# Weihnachtsstern.net
KiCad netlist of a schematic drawn in EAGLE
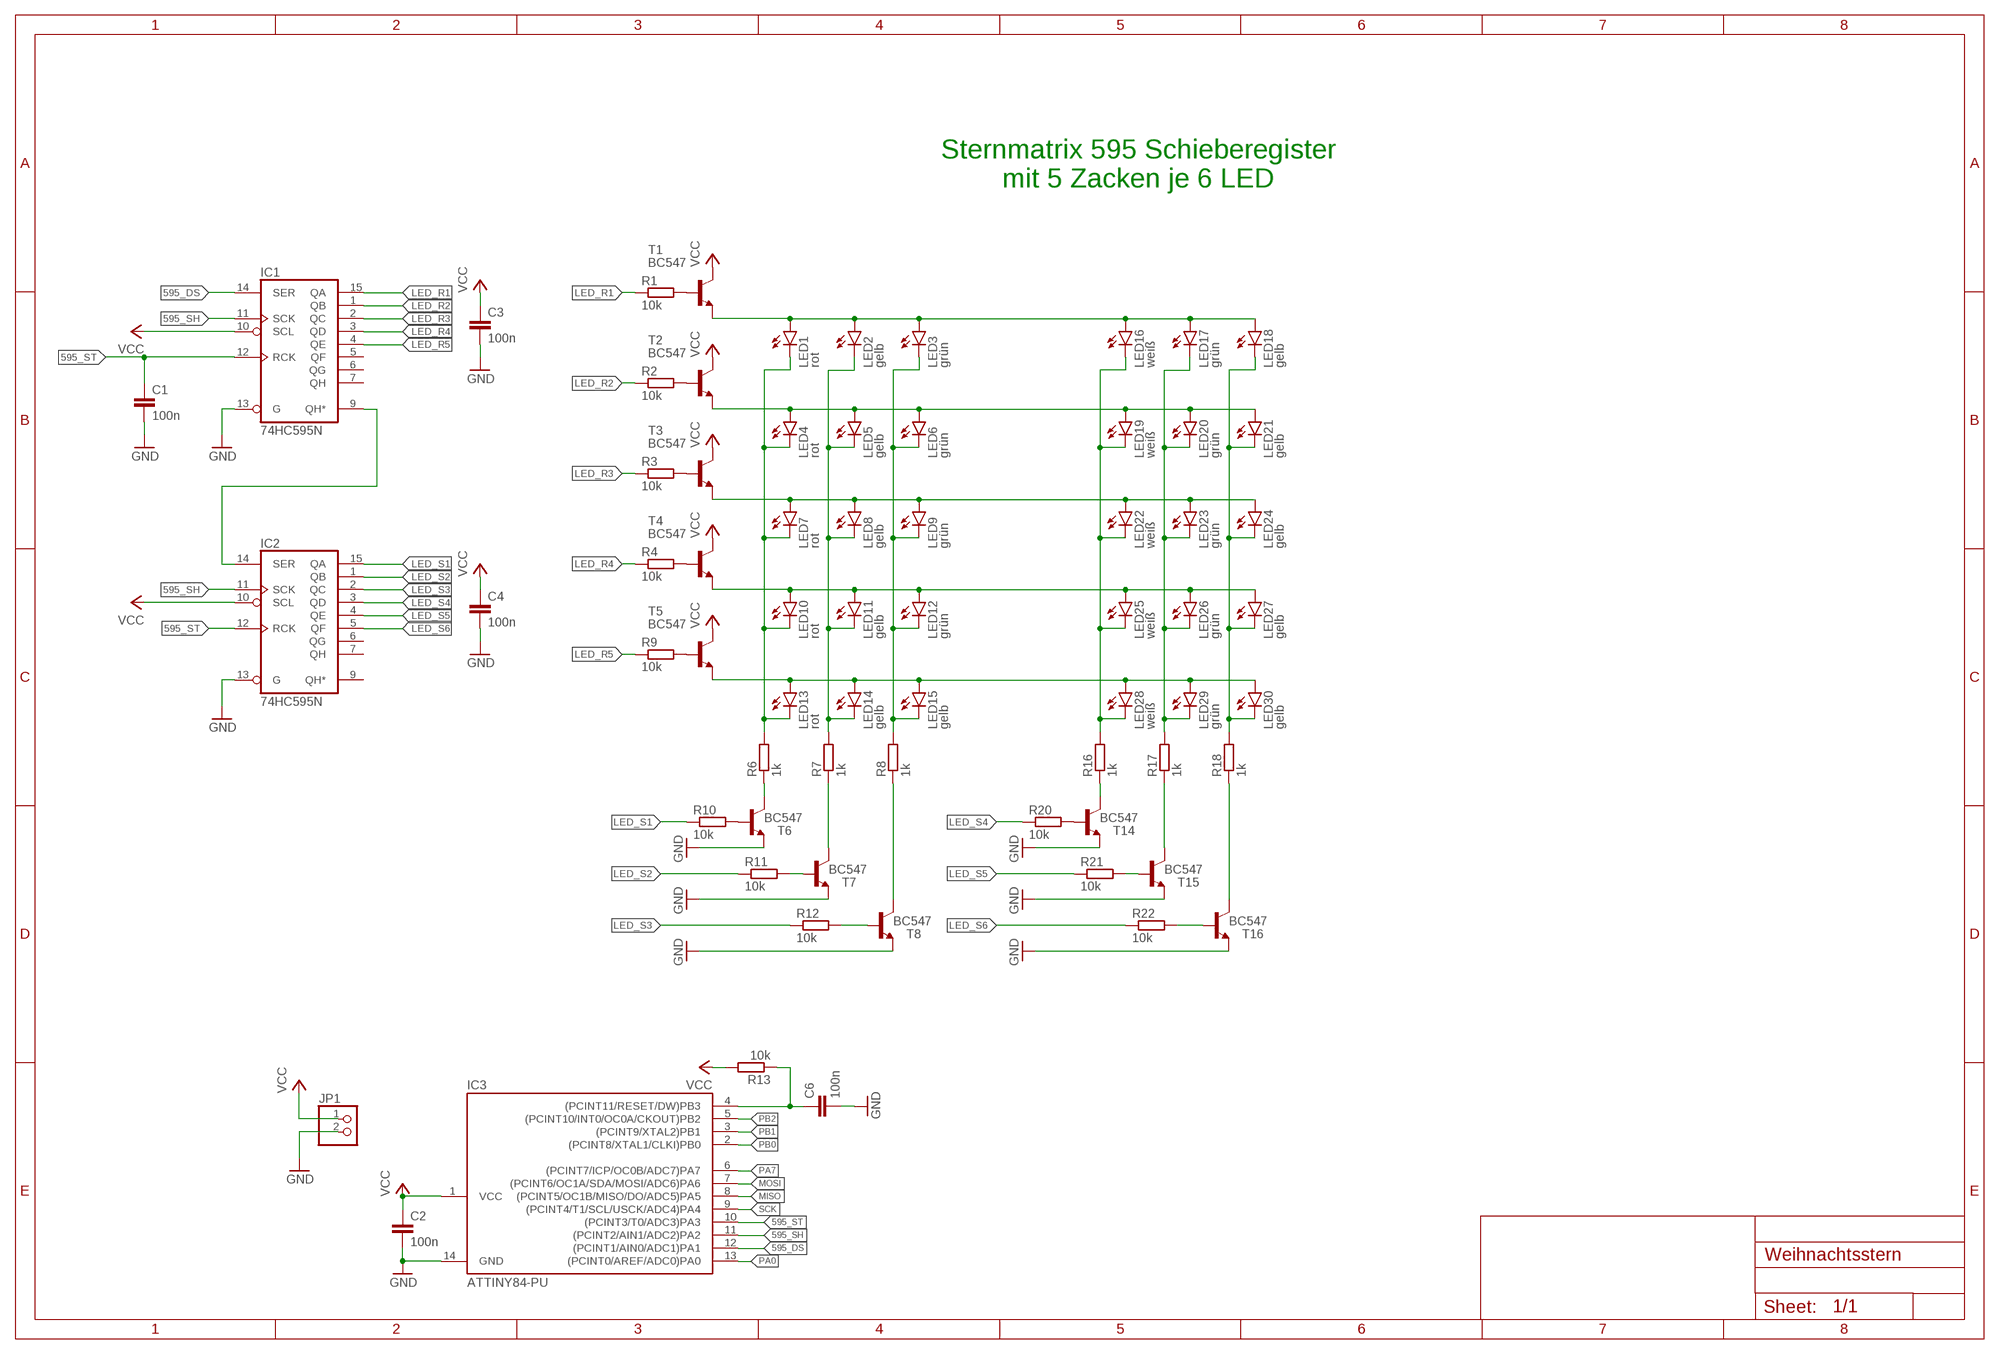
[diagram p0: schematic, sheet 1]

(export (version "E")
  (design (tool "Eeschema 10.0.6"))
  (components
    (comp (ref "C1")
      (value "100n")
      (footprint "eagle-import:C025-024X044")
      (libsource (lib "eagle-import") (part "C-EU025-024X044"))
    )
    (comp (ref "C2")
      (value "100n")
      (footprint "eagle-import:C025-024X044")
      (libsource (lib "eagle-import") (part "C-EU025-024X044"))
    )
    (comp (ref "C3")
      (value "100n")
      (footprint "eagle-import:C025-024X044")
      (libsource (lib "eagle-import") (part "C-EU025-024X044"))
    )
    (comp (ref "C4")
      (value "100n")
      (footprint "eagle-import:C025-024X044")
      (libsource (lib "eagle-import") (part "C-EU025-024X044"))
    )
    (comp (ref "C6")
      (value "100n")
      (footprint "eagle-import:C025-024X044")
      (libsource (lib "eagle-import") (part "C-EU025-024X044"))
    )
    (comp (ref "IC1")
      (value "74HC595N")
      (footprint "eagle-import:DIL16")
      (libsource (lib "eagle-import") (part "74595NHC"))
    )
    (comp (ref "IC2")
      (value "74HC595N")
      (footprint "eagle-import:DIL16")
      (libsource (lib "eagle-import") (part "74595NHC"))
    )
    (comp (ref "IC3")
      (value "ATTINY84-PU")
      (footprint "eagle-import:DIL14")
      (libsource (lib "eagle-import") (part "ATTINY24/44/84-PU"))
    )
    (comp (ref "JP1")
      (value "PINHD-1X2")
      (footprint "eagle-import:1X02")
      (libsource (lib "eagle-import") (part "PINHD-1X2"))
    )
    (comp (ref "LED1")
      (value "rot")
      (footprint "eagle-import:LED3MM")
      (libsource (lib "eagle-import") (part "LED3MM"))
    )
    (comp (ref "LED2")
      (value "gelb")
      (footprint "eagle-import:LED3MM")
      (libsource (lib "eagle-import") (part "LED3MM"))
    )
    (comp (ref "LED3")
      (value "grün")
      (footprint "eagle-import:LED3MM")
      (libsource (lib "eagle-import") (part "LED3MM"))
    )
    (comp (ref "LED4")
      (value "rot")
      (footprint "eagle-import:LED3MM")
      (libsource (lib "eagle-import") (part "LED3MM"))
    )
    (comp (ref "LED5")
      (value "gelb")
      (footprint "eagle-import:LED3MM")
      (libsource (lib "eagle-import") (part "LED3MM"))
    )
    (comp (ref "LED6")
      (value "grün")
      (footprint "eagle-import:LED3MM")
      (libsource (lib "eagle-import") (part "LED3MM"))
    )
    (comp (ref "LED7")
      (value "rot")
      (footprint "eagle-import:LED3MM")
      (libsource (lib "eagle-import") (part "LED3MM"))
    )
    (comp (ref "LED8")
      (value "gelb")
      (footprint "eagle-import:LED3MM")
      (libsource (lib "eagle-import") (part "LED3MM"))
    )
    (comp (ref "LED9")
      (value "grün")
      (footprint "eagle-import:LED3MM")
      (libsource (lib "eagle-import") (part "LED3MM"))
    )
    (comp (ref "LED10")
      (value "rot")
      (footprint "eagle-import:LED3MM")
      (libsource (lib "eagle-import") (part "LED3MM"))
    )
    (comp (ref "LED11")
      (value "gelb")
      (footprint "eagle-import:LED3MM")
      (libsource (lib "eagle-import") (part "LED3MM"))
    )
    (comp (ref "LED12")
      (value "grün")
      (footprint "eagle-import:LED3MM")
      (libsource (lib "eagle-import") (part "LED3MM"))
    )
    (comp (ref "LED13")
      (value "rot")
      (footprint "eagle-import:LED3MM")
      (libsource (lib "eagle-import") (part "LED3MM"))
    )
    (comp (ref "LED14")
      (value "gelb")
      (footprint "eagle-import:LED3MM")
      (libsource (lib "eagle-import") (part "LED3MM"))
    )
    (comp (ref "LED15")
      (value "gelb")
      (footprint "eagle-import:LED3MM")
      (libsource (lib "eagle-import") (part "LED3MM"))
    )
    (comp (ref "LED16")
      (value "weiß")
      (footprint "eagle-import:LED3MM")
      (libsource (lib "eagle-import") (part "LED3MM"))
    )
    (comp (ref "LED17")
      (value "grün")
      (footprint "eagle-import:LED3MM")
      (libsource (lib "eagle-import") (part "LED3MM"))
    )
    (comp (ref "LED18")
      (value "gelb")
      (footprint "eagle-import:LED3MM")
      (libsource (lib "eagle-import") (part "LED3MM"))
    )
    (comp (ref "LED19")
      (value "weiß")
      (footprint "eagle-import:LED3MM")
      (libsource (lib "eagle-import") (part "LED3MM"))
    )
    (comp (ref "LED20")
      (value "grün")
      (footprint "eagle-import:LED3MM")
      (libsource (lib "eagle-import") (part "LED3MM"))
    )
    (comp (ref "LED21")
      (value "gelb")
      (footprint "eagle-import:LED3MM")
      (libsource (lib "eagle-import") (part "LED3MM"))
    )
    (comp (ref "LED22")
      (value "weiß")
      (footprint "eagle-import:LED3MM")
      (libsource (lib "eagle-import") (part "LED3MM"))
    )
    (comp (ref "LED23")
      (value "grün")
      (footprint "eagle-import:LED3MM")
      (libsource (lib "eagle-import") (part "LED3MM"))
    )
    (comp (ref "LED24")
      (value "gelb")
      (footprint "eagle-import:LED3MM")
      (libsource (lib "eagle-import") (part "LED3MM"))
    )
    (comp (ref "LED25")
      (value "weiß")
      (footprint "eagle-import:LED3MM")
      (libsource (lib "eagle-import") (part "LED3MM"))
    )
    (comp (ref "LED26")
      (value "grün")
      (footprint "eagle-import:LED3MM")
      (libsource (lib "eagle-import") (part "LED3MM"))
    )
    (comp (ref "LED27")
      (value "gelb")
      (footprint "eagle-import:LED3MM")
      (libsource (lib "eagle-import") (part "LED3MM"))
    )
    (comp (ref "LED28")
      (value "weiß")
      (footprint "eagle-import:LED3MM")
      (libsource (lib "eagle-import") (part "LED3MM"))
    )
    (comp (ref "LED29")
      (value "grün")
      (footprint "eagle-import:LED3MM")
      (libsource (lib "eagle-import") (part "LED3MM"))
    )
    (comp (ref "LED30")
      (value "gelb")
      (footprint "eagle-import:LED3MM")
      (libsource (lib "eagle-import") (part "LED3MM"))
    )
    (comp (ref "R1")
      (value "10k")
      (footprint "eagle-import:0204_5")
      (libsource (lib "eagle-import") (part "R-EU_0204/5"))
    )
    (comp (ref "R2")
      (value "10k")
      (footprint "eagle-import:0204_5")
      (libsource (lib "eagle-import") (part "R-EU_0204/5"))
    )
    (comp (ref "R3")
      (value "10k")
      (footprint "eagle-import:0204_5")
      (libsource (lib "eagle-import") (part "R-EU_0204/5"))
    )
    (comp (ref "R4")
      (value "10k")
      (footprint "eagle-import:0204_5")
      (libsource (lib "eagle-import") (part "R-EU_0204/5"))
    )
    (comp (ref "R6")
      (value "1k")
      (footprint "eagle-import:0204_5")
      (libsource (lib "eagle-import") (part "R-EU_0204/5"))
    )
    (comp (ref "R7")
      (value "1k")
      (footprint "eagle-import:0204_5")
      (libsource (lib "eagle-import") (part "R-EU_0204/5"))
    )
    (comp (ref "R8")
      (value "1k")
      (footprint "eagle-import:0204_5")
      (libsource (lib "eagle-import") (part "R-EU_0204/5"))
    )
    (comp (ref "R9")
      (value "10k")
      (footprint "eagle-import:0204_5")
      (libsource (lib "eagle-import") (part "R-EU_0204/5"))
    )
    (comp (ref "R10")
      (value "10k")
      (footprint "eagle-import:0204_5")
      (libsource (lib "eagle-import") (part "R-EU_0204/5"))
    )
    (comp (ref "R11")
      (value "10k")
      (footprint "eagle-import:0204_5")
      (libsource (lib "eagle-import") (part "R-EU_0204/5"))
    )
    (comp (ref "R12")
      (value "10k")
      (footprint "eagle-import:0204_5")
      (libsource (lib "eagle-import") (part "R-EU_0204/5"))
    )
    (comp (ref "R13")
      (value "10k")
      (footprint "eagle-import:0204_5")
      (libsource (lib "eagle-import") (part "R-EU_0204/5"))
    )
    (comp (ref "R16")
      (value "1k")
      (footprint "eagle-import:0204_5")
      (libsource (lib "eagle-import") (part "R-EU_0204/5"))
    )
    (comp (ref "R17")
      (value "1k")
      (footprint "eagle-import:0204_5")
      (libsource (lib "eagle-import") (part "R-EU_0204/5"))
    )
    (comp (ref "R18")
      (value "1k")
      (footprint "eagle-import:0204_5")
      (libsource (lib "eagle-import") (part "R-EU_0204/5"))
    )
    (comp (ref "R20")
      (value "10k")
      (footprint "eagle-import:0204_5")
      (libsource (lib "eagle-import") (part "R-EU_0204/5"))
    )
    (comp (ref "R21")
      (value "10k")
      (footprint "eagle-import:0204_5")
      (libsource (lib "eagle-import") (part "R-EU_0204/5"))
    )
    (comp (ref "R22")
      (value "10k")
      (footprint "eagle-import:0204_5")
      (libsource (lib "eagle-import") (part "R-EU_0204/5"))
    )
    (comp (ref "T1")
      (value "BC547")
      (footprint "eagle-import:TO92")
      (libsource (lib "eagle-import") (part "BC547"))
    )
    (comp (ref "T2")
      (value "BC547")
      (footprint "eagle-import:TO92")
      (libsource (lib "eagle-import") (part "BC547"))
    )
    (comp (ref "T3")
      (value "BC547")
      (footprint "eagle-import:TO92")
      (libsource (lib "eagle-import") (part "BC547"))
    )
    (comp (ref "T4")
      (value "BC547")
      (footprint "eagle-import:TO92")
      (libsource (lib "eagle-import") (part "BC547"))
    )
    (comp (ref "T5")
      (value "BC547")
      (footprint "eagle-import:TO92")
      (libsource (lib "eagle-import") (part "-NPN-TO92"))
    )
    (comp (ref "T6")
      (value "BC547")
      (footprint "eagle-import:TO92")
      (libsource (lib "eagle-import") (part "BC547"))
    )
    (comp (ref "T7")
      (value "BC547")
      (footprint "eagle-import:TO92")
      (libsource (lib "eagle-import") (part "BC547"))
    )
    (comp (ref "T8")
      (value "BC547")
      (footprint "eagle-import:TO92")
      (libsource (lib "eagle-import") (part "BC547"))
    )
    (comp (ref "T14")
      (value "BC547")
      (footprint "eagle-import:TO92")
      (libsource (lib "eagle-import") (part "BC547"))
    )
    (comp (ref "T15")
      (value "BC547")
      (footprint "eagle-import:TO92")
      (libsource (lib "eagle-import") (part "BC547"))
    )
    (comp (ref "T16")
      (value "BC547")
      (footprint "eagle-import:TO92")
      (libsource (lib "eagle-import") (part "BC547"))
    )
  )
  (nets
    (net (code "1") (name "595_DS") (class "Default")
      (node (ref "IC1") (pin "14") (pinfunction "SER_14") (pintype "input"))
      (node (ref "IC3") (pin "12") (pinfunction "(PCINT1/AIN0/ADC1)PA1_12") (pintype "bidirectional"))
    )
    (net (code "2") (name "595_SH") (class "Default")
      (node (ref "IC1") (pin "11") (pinfunction "SCK_11") (pintype "input"))
      (node (ref "IC2") (pin "11") (pinfunction "SCK_11") (pintype "input"))
      (node (ref "IC3") (pin "11") (pinfunction "(PCINT2/AIN1/ADC2)PA2_11") (pintype "bidirectional"))
    )
    (net (code "3") (name "595_ST") (class "Default")
      (node (ref "C1") (pin "1") (pinfunction "1_1") (pintype "passive"))
      (node (ref "IC1") (pin "12") (pinfunction "RCK_12") (pintype "input"))
      (node (ref "IC2") (pin "12") (pinfunction "RCK_12") (pintype "input"))
      (node (ref "IC3") (pin "10") (pinfunction "(PCINT3/T0/ADC3)PA3_10") (pintype "bidirectional"))
    )
    (net (code "4") (name "GND") (class "Default")
      (node (ref "C1") (pin "2") (pinfunction "2_2") (pintype "passive"))
      (node (ref "C2") (pin "2") (pinfunction "2_2") (pintype "passive"))
      (node (ref "C3") (pin "2") (pinfunction "2_2") (pintype "passive"))
      (node (ref "C4") (pin "2") (pinfunction "2_2") (pintype "passive"))
      (node (ref "C6") (pin "2") (pinfunction "2_2") (pintype "passive"))
      (node (ref "IC1") (pin "13") (pinfunction "G_13") (pintype "input"))
      (node (ref "IC2") (pin "13") (pinfunction "G_13") (pintype "input"))
      (node (ref "IC3") (pin "14") (pinfunction "GND_14") (pintype "power_in"))
      (node (ref "JP1") (pin "2") (pinfunction "2_2") (pintype "passive"))
      (node (ref "T14") (pin "1") (pinfunction "E_1") (pintype "passive"))
      (node (ref "T15") (pin "1") (pinfunction "E_1") (pintype "passive"))
      (node (ref "T16") (pin "1") (pinfunction "E_1") (pintype "passive"))
      (node (ref "T6") (pin "1") (pinfunction "E_1") (pintype "passive"))
      (node (ref "T7") (pin "1") (pinfunction "E_1") (pintype "passive"))
      (node (ref "T8") (pin "1") (pinfunction "E_1") (pintype "passive"))
    )
    (net (code "5") (name "LED_R1") (class "Default")
      (node (ref "IC1") (pin "15") (pinfunction "QA_15") (pintype "tri_state"))
      (node (ref "R1") (pin "1") (pinfunction "1_1") (pintype "passive"))
    )
    (net (code "6") (name "LED_R2") (class "Default")
      (node (ref "IC1") (pin "1") (pinfunction "QB_1") (pintype "tri_state"))
      (node (ref "R2") (pin "1") (pinfunction "1_1") (pintype "passive"))
    )
    (net (code "7") (name "LED_R3") (class "Default")
      (node (ref "IC1") (pin "2") (pinfunction "QC_2") (pintype "tri_state"))
      (node (ref "R3") (pin "1") (pinfunction "1_1") (pintype "passive"))
    )
    (net (code "8") (name "LED_R4") (class "Default")
      (node (ref "IC1") (pin "3") (pinfunction "QD_3") (pintype "tri_state"))
      (node (ref "R4") (pin "1") (pinfunction "1_1") (pintype "passive"))
    )
    (net (code "9") (name "LED_R5") (class "Default")
      (node (ref "IC1") (pin "4") (pinfunction "QE_4") (pintype "tri_state"))
      (node (ref "R9") (pin "1") (pinfunction "1_1") (pintype "passive"))
    )
    (net (code "10") (name "LED_S1") (class "Default")
      (node (ref "IC2") (pin "15") (pinfunction "QA_15") (pintype "tri_state"))
      (node (ref "R10") (pin "1") (pinfunction "1_1") (pintype "passive"))
    )
    (net (code "11") (name "LED_S2") (class "Default")
      (node (ref "IC2") (pin "1") (pinfunction "QB_1") (pintype "tri_state"))
      (node (ref "R11") (pin "1") (pinfunction "1_1") (pintype "passive"))
    )
    (net (code "12") (name "LED_S3") (class "Default")
      (node (ref "IC2") (pin "2") (pinfunction "QC_2") (pintype "tri_state"))
      (node (ref "R12") (pin "1") (pinfunction "1_1") (pintype "passive"))
    )
    (net (code "13") (name "LED_S4") (class "Default")
      (node (ref "IC2") (pin "3") (pinfunction "QD_3") (pintype "tri_state"))
      (node (ref "R20") (pin "1") (pinfunction "1_1") (pintype "passive"))
    )
    (net (code "14") (name "LED_S5") (class "Default")
      (node (ref "IC2") (pin "4") (pinfunction "QE_4") (pintype "tri_state"))
      (node (ref "R21") (pin "1") (pinfunction "1_1") (pintype "passive"))
    )
    (net (code "15") (name "LED_S6") (class "Default")
      (node (ref "IC2") (pin "5") (pinfunction "QF_5") (pintype "tri_state"))
      (node (ref "R22") (pin "1") (pinfunction "1_1") (pintype "passive"))
    )
    (net (code "16") (name "MISO") (class "Default")
      (node (ref "IC3") (pin "8") (pinfunction "(PCINT5/OC1B/MISO/DO/ADC5)PA5_8") (pintype "bidirectional"))
    )
    (net (code "17") (name "MOSI") (class "Default")
      (node (ref "IC3") (pin "7") (pinfunction "(PCINT6/OC1A/SDA/MOSI/ADC6)PA6_7") (pintype "bidirectional"))
    )
    (net (code "18") (name "Net-(IC1A-QH*)") (class "Default")
      (node (ref "IC1") (pin "9") (pinfunction "QH*_9") (pintype "tri_state"))
      (node (ref "IC2") (pin "14") (pinfunction "SER_14") (pintype "input"))
    )
    (net (code "19") (name "Net-(IC3-(PCINT11{slash}RESET{slash}DW)PB3)") (class "Default")
      (node (ref "C6") (pin "1") (pinfunction "1_1") (pintype "passive"))
      (node (ref "IC3") (pin "4") (pinfunction "(PCINT11/RESET/DW)PB3_4") (pintype "bidirectional"))
      (node (ref "R13") (pin "1") (pinfunction "1_1") (pintype "passive"))
    )
    (net (code "20") (name "Net-(LED1-C)") (class "Default")
      (node (ref "LED1") (pin "K") (pinfunction "C_K") (pintype "passive"))
      (node (ref "LED10") (pin "K") (pinfunction "C_K") (pintype "passive"))
      (node (ref "LED13") (pin "K") (pinfunction "C_K") (pintype "passive"))
      (node (ref "LED4") (pin "K") (pinfunction "C_K") (pintype "passive"))
      (node (ref "LED7") (pin "K") (pinfunction "C_K") (pintype "passive"))
      (node (ref "R6") (pin "2") (pinfunction "2_2") (pintype "passive"))
    )
    (net (code "21") (name "Net-(LED11-C)") (class "Default")
      (node (ref "LED11") (pin "K") (pinfunction "C_K") (pintype "passive"))
      (node (ref "LED14") (pin "K") (pinfunction "C_K") (pintype "passive"))
      (node (ref "LED2") (pin "K") (pinfunction "C_K") (pintype "passive"))
      (node (ref "LED5") (pin "K") (pinfunction "C_K") (pintype "passive"))
      (node (ref "LED8") (pin "K") (pinfunction "C_K") (pintype "passive"))
      (node (ref "R7") (pin "2") (pinfunction "2_2") (pintype "passive"))
    )
    (net (code "22") (name "Net-(LED12-C)") (class "Default")
      (node (ref "LED12") (pin "K") (pinfunction "C_K") (pintype "passive"))
      (node (ref "LED15") (pin "K") (pinfunction "C_K") (pintype "passive"))
      (node (ref "LED3") (pin "K") (pinfunction "C_K") (pintype "passive"))
      (node (ref "LED6") (pin "K") (pinfunction "C_K") (pintype "passive"))
      (node (ref "LED9") (pin "K") (pinfunction "C_K") (pintype "passive"))
      (node (ref "R8") (pin "2") (pinfunction "2_2") (pintype "passive"))
    )
    (net (code "23") (name "Net-(LED16-C)") (class "Default")
      (node (ref "LED16") (pin "K") (pinfunction "C_K") (pintype "passive"))
      (node (ref "LED19") (pin "K") (pinfunction "C_K") (pintype "passive"))
      (node (ref "LED22") (pin "K") (pinfunction "C_K") (pintype "passive"))
      (node (ref "LED25") (pin "K") (pinfunction "C_K") (pintype "passive"))
      (node (ref "LED28") (pin "K") (pinfunction "C_K") (pintype "passive"))
      (node (ref "R16") (pin "2") (pinfunction "2_2") (pintype "passive"))
    )
    (net (code "24") (name "Net-(LED17-C)") (class "Default")
      (node (ref "LED17") (pin "K") (pinfunction "C_K") (pintype "passive"))
      (node (ref "LED20") (pin "K") (pinfunction "C_K") (pintype "passive"))
      (node (ref "LED23") (pin "K") (pinfunction "C_K") (pintype "passive"))
      (node (ref "LED26") (pin "K") (pinfunction "C_K") (pintype "passive"))
      (node (ref "LED29") (pin "K") (pinfunction "C_K") (pintype "passive"))
      (node (ref "R17") (pin "2") (pinfunction "2_2") (pintype "passive"))
    )
    (net (code "25") (name "Net-(LED18-C)") (class "Default")
      (node (ref "LED18") (pin "K") (pinfunction "C_K") (pintype "passive"))
      (node (ref "LED21") (pin "K") (pinfunction "C_K") (pintype "passive"))
      (node (ref "LED24") (pin "K") (pinfunction "C_K") (pintype "passive"))
      (node (ref "LED27") (pin "K") (pinfunction "C_K") (pintype "passive"))
      (node (ref "LED30") (pin "K") (pinfunction "C_K") (pintype "passive"))
      (node (ref "R18") (pin "2") (pinfunction "2_2") (pintype "passive"))
    )
    (net (code "26") (name "Net-(T1-B)") (class "Default")
      (node (ref "R1") (pin "2") (pinfunction "2_2") (pintype "passive"))
      (node (ref "T1") (pin "2") (pinfunction "B_2") (pintype "passive"))
    )
    (net (code "27") (name "Net-(T1-E)") (class "Default")
      (node (ref "LED1") (pin "A") (pinfunction "A_A") (pintype "passive"))
      (node (ref "LED16") (pin "A") (pinfunction "A_A") (pintype "passive"))
      (node (ref "LED17") (pin "A") (pinfunction "A_A") (pintype "passive"))
      (node (ref "LED18") (pin "A") (pinfunction "A_A") (pintype "passive"))
      (node (ref "LED2") (pin "A") (pinfunction "A_A") (pintype "passive"))
      (node (ref "LED3") (pin "A") (pinfunction "A_A") (pintype "passive"))
      (node (ref "T1") (pin "1") (pinfunction "E_1") (pintype "passive"))
    )
    (net (code "28") (name "Net-(T2-B)") (class "Default")
      (node (ref "R2") (pin "2") (pinfunction "2_2") (pintype "passive"))
      (node (ref "T2") (pin "2") (pinfunction "B_2") (pintype "passive"))
    )
    (net (code "29") (name "Net-(T2-E)") (class "Default")
      (node (ref "LED19") (pin "A") (pinfunction "A_A") (pintype "passive"))
      (node (ref "LED20") (pin "A") (pinfunction "A_A") (pintype "passive"))
      (node (ref "LED21") (pin "A") (pinfunction "A_A") (pintype "passive"))
      (node (ref "LED4") (pin "A") (pinfunction "A_A") (pintype "passive"))
      (node (ref "LED5") (pin "A") (pinfunction "A_A") (pintype "passive"))
      (node (ref "LED6") (pin "A") (pinfunction "A_A") (pintype "passive"))
      (node (ref "T2") (pin "1") (pinfunction "E_1") (pintype "passive"))
    )
    (net (code "30") (name "Net-(T3-B)") (class "Default")
      (node (ref "R3") (pin "2") (pinfunction "2_2") (pintype "passive"))
      (node (ref "T3") (pin "2") (pinfunction "B_2") (pintype "passive"))
    )
    (net (code "31") (name "Net-(T3-E)") (class "Default")
      (node (ref "LED22") (pin "A") (pinfunction "A_A") (pintype "passive"))
      (node (ref "LED23") (pin "A") (pinfunction "A_A") (pintype "passive"))
      (node (ref "LED24") (pin "A") (pinfunction "A_A") (pintype "passive"))
      (node (ref "LED7") (pin "A") (pinfunction "A_A") (pintype "passive"))
      (node (ref "LED8") (pin "A") (pinfunction "A_A") (pintype "passive"))
      (node (ref "LED9") (pin "A") (pinfunction "A_A") (pintype "passive"))
      (node (ref "T3") (pin "1") (pinfunction "E_1") (pintype "passive"))
    )
    (net (code "32") (name "Net-(T4-B)") (class "Default")
      (node (ref "R4") (pin "2") (pinfunction "2_2") (pintype "passive"))
      (node (ref "T4") (pin "2") (pinfunction "B_2") (pintype "passive"))
    )
    (net (code "33") (name "Net-(T4-E)") (class "Default")
      (node (ref "LED10") (pin "A") (pinfunction "A_A") (pintype "passive"))
      (node (ref "LED11") (pin "A") (pinfunction "A_A") (pintype "passive"))
      (node (ref "LED12") (pin "A") (pinfunction "A_A") (pintype "passive"))
      (node (ref "LED25") (pin "A") (pinfunction "A_A") (pintype "passive"))
      (node (ref "LED26") (pin "A") (pinfunction "A_A") (pintype "passive"))
      (node (ref "LED27") (pin "A") (pinfunction "A_A") (pintype "passive"))
      (node (ref "T4") (pin "1") (pinfunction "E_1") (pintype "passive"))
    )
    (net (code "34") (name "Net-(T5-B)") (class "Default")
      (node (ref "R9") (pin "2") (pinfunction "2_2") (pintype "passive"))
      (node (ref "T5") (pin "2") (pinfunction "B_2") (pintype "passive"))
    )
    (net (code "35") (name "Net-(T5-E)") (class "Default")
      (node (ref "LED13") (pin "A") (pinfunction "A_A") (pintype "passive"))
      (node (ref "LED14") (pin "A") (pinfunction "A_A") (pintype "passive"))
      (node (ref "LED15") (pin "A") (pinfunction "A_A") (pintype "passive"))
      (node (ref "LED28") (pin "A") (pinfunction "A_A") (pintype "passive"))
      (node (ref "LED29") (pin "A") (pinfunction "A_A") (pintype "passive"))
      (node (ref "LED30") (pin "A") (pinfunction "A_A") (pintype "passive"))
      (node (ref "T5") (pin "1") (pinfunction "E_1") (pintype "passive"))
    )
    (net (code "36") (name "Net-(T6-B)") (class "Default")
      (node (ref "R10") (pin "2") (pinfunction "2_2") (pintype "passive"))
      (node (ref "T6") (pin "2") (pinfunction "B_2") (pintype "passive"))
    )
    (net (code "37") (name "Net-(T6-C)") (class "Default")
      (node (ref "R6") (pin "1") (pinfunction "1_1") (pintype "passive"))
      (node (ref "T6") (pin "3") (pinfunction "C_3") (pintype "passive"))
    )
    (net (code "38") (name "Net-(T7-B)") (class "Default")
      (node (ref "R11") (pin "2") (pinfunction "2_2") (pintype "passive"))
      (node (ref "T7") (pin "2") (pinfunction "B_2") (pintype "passive"))
    )
    (net (code "39") (name "Net-(T7-C)") (class "Default")
      (node (ref "R7") (pin "1") (pinfunction "1_1") (pintype "passive"))
      (node (ref "T7") (pin "3") (pinfunction "C_3") (pintype "passive"))
    )
    (net (code "40") (name "Net-(T8-B)") (class "Default")
      (node (ref "R12") (pin "2") (pinfunction "2_2") (pintype "passive"))
      (node (ref "T8") (pin "2") (pinfunction "B_2") (pintype "passive"))
    )
    (net (code "41") (name "Net-(T8-C)") (class "Default")
      (node (ref "R8") (pin "1") (pinfunction "1_1") (pintype "passive"))
      (node (ref "T8") (pin "3") (pinfunction "C_3") (pintype "passive"))
    )
    (net (code "42") (name "Net-(T14-B)") (class "Default")
      (node (ref "R20") (pin "2") (pinfunction "2_2") (pintype "passive"))
      (node (ref "T14") (pin "2") (pinfunction "B_2") (pintype "passive"))
    )
    (net (code "43") (name "Net-(T14-C)") (class "Default")
      (node (ref "R16") (pin "1") (pinfunction "1_1") (pintype "passive"))
      (node (ref "T14") (pin "3") (pinfunction "C_3") (pintype "passive"))
    )
    (net (code "44") (name "Net-(T15-B)") (class "Default")
      (node (ref "R21") (pin "2") (pinfunction "2_2") (pintype "passive"))
      (node (ref "T15") (pin "2") (pinfunction "B_2") (pintype "passive"))
    )
    (net (code "45") (name "Net-(T15-C)") (class "Default")
      (node (ref "R17") (pin "1") (pinfunction "1_1") (pintype "passive"))
      (node (ref "T15") (pin "3") (pinfunction "C_3") (pintype "passive"))
    )
    (net (code "46") (name "Net-(T16-B)") (class "Default")
      (node (ref "R22") (pin "2") (pinfunction "2_2") (pintype "passive"))
      (node (ref "T16") (pin "2") (pinfunction "B_2") (pintype "passive"))
    )
    (net (code "47") (name "Net-(T16-C)") (class "Default")
      (node (ref "R18") (pin "1") (pinfunction "1_1") (pintype "passive"))
      (node (ref "T16") (pin "3") (pinfunction "C_3") (pintype "passive"))
    )
    (net (code "48") (name "PA0") (class "Default")
      (node (ref "IC3") (pin "13") (pinfunction "(PCINT0/AREF/ADC0)PA0_13") (pintype "bidirectional"))
    )
    (net (code "49") (name "PA7") (class "Default")
      (node (ref "IC3") (pin "6") (pinfunction "(PCINT7/ICP/OC0B/ADC7)PA7_6") (pintype "bidirectional"))
    )
    (net (code "50") (name "PB0") (class "Default")
      (node (ref "IC3") (pin "2") (pinfunction "(PCINT8/XTAL1/CLKI)PB0_2") (pintype "bidirectional"))
    )
    (net (code "51") (name "PB1") (class "Default")
      (node (ref "IC3") (pin "3") (pinfunction "(PCINT9/XTAL2)PB1_3") (pintype "bidirectional"))
    )
    (net (code "52") (name "PB2") (class "Default")
      (node (ref "IC3") (pin "5") (pinfunction "(PCINT10/INT0/OC0A/CKOUT)PB2_5") (pintype "bidirectional"))
    )
    (net (code "53") (name "SCK") (class "Default")
      (node (ref "IC3") (pin "9") (pinfunction "(PCINT4/T1/SCL/USCK/ADC4)PA4_9") (pintype "bidirectional"))
    )
    (net (code "54") (name "VCC") (class "Default")
      (node (ref "C2") (pin "1") (pinfunction "1_1") (pintype "passive"))
      (node (ref "C3") (pin "1") (pinfunction "1_1") (pintype "passive"))
      (node (ref "C4") (pin "1") (pinfunction "1_1") (pintype "passive"))
      (node (ref "IC1") (pin "10") (pinfunction "SCL_10") (pintype "input"))
      (node (ref "IC2") (pin "10") (pinfunction "SCL_10") (pintype "input"))
      (node (ref "IC3") (pin "1") (pinfunction "VCC_1") (pintype "power_in"))
      (node (ref "JP1") (pin "1") (pinfunction "1_1") (pintype "passive"))
      (node (ref "R13") (pin "2") (pinfunction "2_2") (pintype "passive"))
      (node (ref "T1") (pin "3") (pinfunction "C_3") (pintype "passive"))
      (node (ref "T2") (pin "3") (pinfunction "C_3") (pintype "passive"))
      (node (ref "T3") (pin "3") (pinfunction "C_3") (pintype "passive"))
      (node (ref "T4") (pin "3") (pinfunction "C_3") (pintype "passive"))
      (node (ref "T5") (pin "3") (pinfunction "C_3") (pintype "passive"))
    )
    (net (code "55") (name "unconnected-(IC1A-QF-Pad5)") (class "Default")
      (node (ref "IC1") (pin "5") (pinfunction "QF_5") (pintype "tri_state"))
    )
    (net (code "56") (name "unconnected-(IC1A-QG-Pad6)") (class "Default")
      (node (ref "IC1") (pin "6") (pinfunction "QG_6") (pintype "tri_state"))
    )
    (net (code "57") (name "unconnected-(IC1A-QH-Pad7)") (class "Default")
      (node (ref "IC1") (pin "7") (pinfunction "QH_7") (pintype "tri_state"))
    )
    (net (code "58") (name "unconnected-(IC2A-QG-Pad6)") (class "Default")
      (node (ref "IC2") (pin "6") (pinfunction "QG_6") (pintype "tri_state"))
    )
    (net (code "59") (name "unconnected-(IC2A-QH*-Pad9)") (class "Default")
      (node (ref "IC2") (pin "9") (pinfunction "QH*_9") (pintype "tri_state"))
    )
    (net (code "60") (name "unconnected-(IC2A-QH-Pad7)") (class "Default")
      (node (ref "IC2") (pin "7") (pinfunction "QH_7") (pintype "tri_state"))
    )
  )
)
